# power_ver3.net
KiCad netlist of a schematic drawn in EAGLE
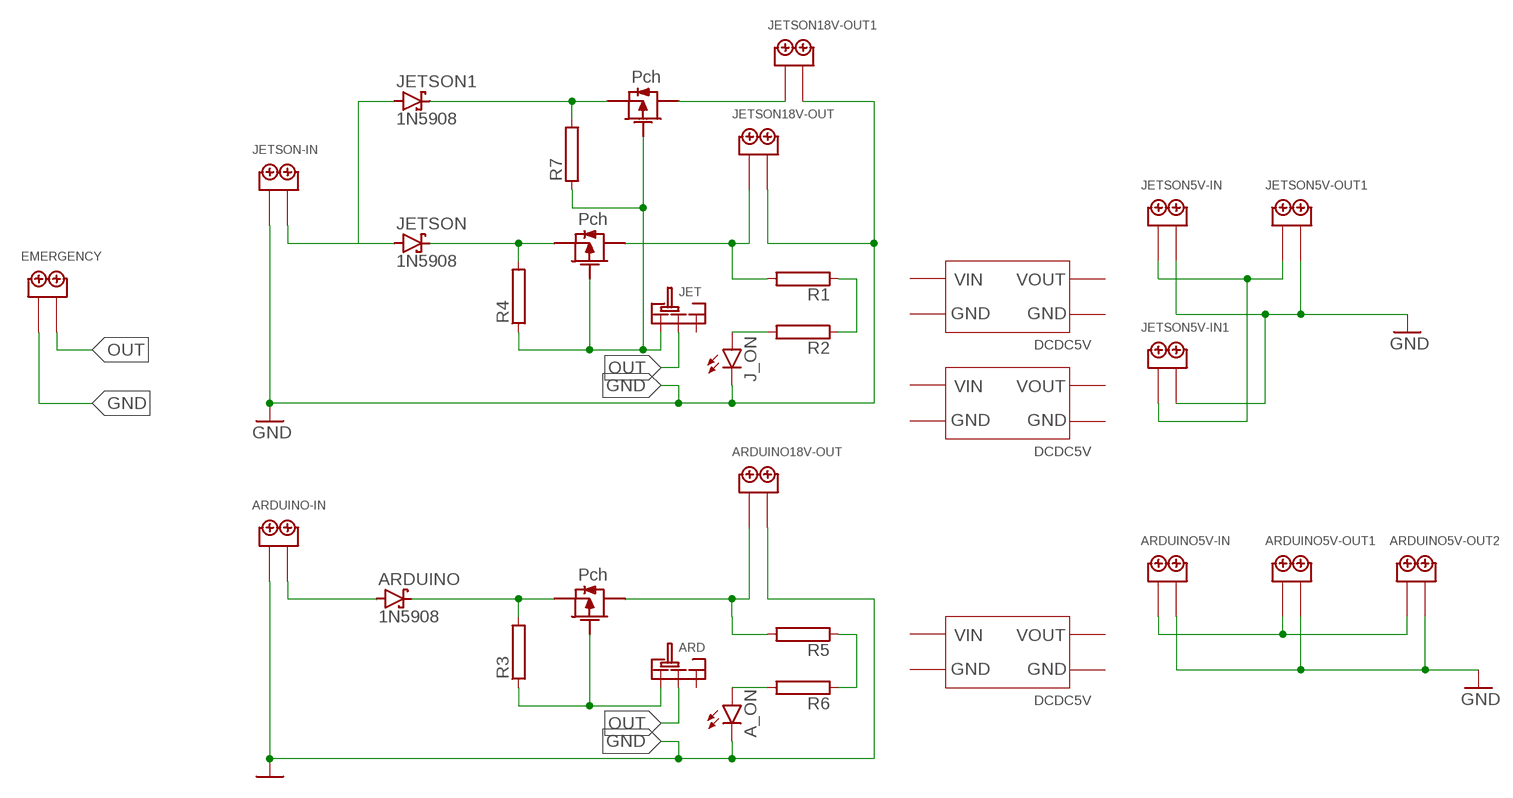
[diagram p0: schematic, sheet 1]

(export (version "E")
  (design (tool "Eeschema 10.0.6"))
  (components
    (comp (ref "ARD")
      (value "SRIDE_SWITCH")
      (footprint "eagle-import:SRIDE_SWITCH")
      (libsource (lib "eagle-import") (part "SRIDE_SWITCH"))
    )
    (comp (ref "ARDUINO")
      (value "1N5908")
      (footprint "eagle-import:C4111-15")
      (libsource (lib "eagle-import") (part "1N5908"))
    )
    (comp (ref "ARDUINO-IN")
      (value "2PIN")
      (footprint "eagle-import:2PIN")
      (libsource (lib "eagle-import") (part "2PIN"))
    )
    (comp (ref "ARDUINO5V-IN")
      (value "2PIN")
      (footprint "eagle-import:2PIN")
      (libsource (lib "eagle-import") (part "2PIN"))
    )
    (comp (ref "ARDUINO5V-OUT1")
      (value "2PIN")
      (footprint "eagle-import:2PIN")
      (libsource (lib "eagle-import") (part "2PIN"))
    )
    (comp (ref "ARDUINO5V-OUT2")
      (value "2PIN")
      (footprint "eagle-import:2PIN")
      (libsource (lib "eagle-import") (part "2PIN"))
    )
    (comp (ref "ARDUINO18V-OUT")
      (value "2PIN")
      (footprint "eagle-import:2PIN")
      (libsource (lib "eagle-import") (part "2PIN"))
    )
    (comp (ref "A_ON")
      (value "LED5MM")
      (footprint "eagle-import:LED5MM")
      (libsource (lib "eagle-import") (part "LED5MM"))
    )
    (comp (ref "EMERGENCY")
      (value "2PIN")
      (footprint "eagle-import:2PIN")
      (libsource (lib "eagle-import") (part "2PIN"))
    )
    (comp (ref "JET")
      (value "SRIDE_SWITCH")
      (footprint "eagle-import:SRIDE_SWITCH")
      (libsource (lib "eagle-import") (part "SRIDE_SWITCH"))
    )
    (comp (ref "JETSON")
      (value "1N5908")
      (footprint "eagle-import:C4111-15")
      (libsource (lib "eagle-import") (part "1N5908"))
    )
    (comp (ref "JETSON-IN")
      (value "2PIN")
      (footprint "eagle-import:2PIN")
      (libsource (lib "eagle-import") (part "2PIN"))
    )
    (comp (ref "JETSON1")
      (value "1N5908")
      (footprint "eagle-import:C4111-15")
      (libsource (lib "eagle-import") (part "1N5908"))
    )
    (comp (ref "JETSON5V-IN")
      (value "2PIN")
      (footprint "eagle-import:2PIN")
      (libsource (lib "eagle-import") (part "2PIN"))
    )
    (comp (ref "JETSON5V-IN1")
      (value "2PIN")
      (footprint "eagle-import:2PIN")
      (libsource (lib "eagle-import") (part "2PIN"))
    )
    (comp (ref "JETSON5V-OUT1")
      (value "2PIN")
      (footprint "eagle-import:2PIN")
      (libsource (lib "eagle-import") (part "2PIN"))
    )
    (comp (ref "JETSON18V-OUT")
      (value "2PIN")
      (footprint "eagle-import:2PIN")
      (libsource (lib "eagle-import") (part "2PIN"))
    )
    (comp (ref "JETSON18V-OUT1")
      (value "2PIN")
      (footprint "eagle-import:2PIN")
      (libsource (lib "eagle-import") (part "2PIN"))
    )
    (comp (ref "J_ON")
      (value "LED5MM")
      (footprint "eagle-import:LED5MM")
      (libsource (lib "eagle-import") (part "LED5MM"))
    )
    (comp (ref "R1")
      (value "RAC01")
      (footprint "eagle-import:AC01")
      (libsource (lib "eagle-import") (part "RAC01"))
    )
    (comp (ref "R2")
      (value "RAC01")
      (footprint "eagle-import:AC01")
      (libsource (lib "eagle-import") (part "RAC01"))
    )
    (comp (ref "R3")
      (value "RAC01")
      (footprint "eagle-import:AC01")
      (libsource (lib "eagle-import") (part "RAC01"))
    )
    (comp (ref "R4")
      (value "RAC01")
      (footprint "eagle-import:AC01")
      (libsource (lib "eagle-import") (part "RAC01"))
    )
    (comp (ref "R5")
      (value "RAC01")
      (footprint "eagle-import:AC01")
      (libsource (lib "eagle-import") (part "RAC01"))
    )
    (comp (ref "R6")
      (value "RAC01")
      (footprint "eagle-import:AC01")
      (libsource (lib "eagle-import") (part "RAC01"))
    )
    (comp (ref "R7")
      (value "RAC01")
      (footprint "eagle-import:AC01")
      (libsource (lib "eagle-import") (part "RAC01"))
    )
    (comp (ref "U$1")
      (value "2SJ334")
      (footprint "eagle-import:2SJ334")
      (libsource (lib "eagle-import") (part "2SJ334"))
    )
    (comp (ref "U$2")
      (value "DCDCDEV")
      (footprint "eagle-import:DCDCDEV")
      (libsource (lib "eagle-import") (part "DCDCDEV"))
    )
    (comp (ref "U$4")
      (value "2SJ334")
      (footprint "eagle-import:2SJ334")
      (libsource (lib "eagle-import") (part "2SJ334"))
    )
    (comp (ref "U$5")
      (value "2SJ334")
      (footprint "eagle-import:2SJ334")
      (libsource (lib "eagle-import") (part "2SJ334"))
    )
    (comp (ref "U$6")
      (value "DCDCDEV")
      (footprint "eagle-import:DCDCDEV")
      (libsource (lib "eagle-import") (part "DCDCDEV"))
    )
    (comp (ref "U$23")
      (value "DCDCDEV")
      (footprint "eagle-import:DCDCDEV")
      (libsource (lib "eagle-import") (part "DCDCDEV"))
    )
  )
  (nets
    (net (code "1") (name "GND") (class "Default")
      (node (ref "ARDUINO-IN") (pin "P$1") (pinfunction "P$1_P$1") (pintype "bidirectional"))
      (node (ref "ARDUINO18V-OUT") (pin "P$2") (pinfunction "P$2_P$2") (pintype "bidirectional"))
      (node (ref "ARDUINO5V-IN") (pin "P$2") (pinfunction "P$2_P$2") (pintype "bidirectional"))
      (node (ref "ARDUINO5V-OUT1") (pin "P$2") (pinfunction "P$2_P$2") (pintype "bidirectional"))
      (node (ref "ARDUINO5V-OUT2") (pin "P$2") (pinfunction "P$2_P$2") (pintype "bidirectional"))
      (node (ref "A_ON") (pin "K") (pinfunction "C_K") (pintype "passive"))
      (node (ref "EMERGENCY") (pin "P$1") (pinfunction "P$1_P$1") (pintype "bidirectional"))
      (node (ref "JETSON-IN") (pin "P$1") (pinfunction "P$1_P$1") (pintype "bidirectional"))
      (node (ref "JETSON18V-OUT") (pin "P$2") (pinfunction "P$2_P$2") (pintype "bidirectional"))
      (node (ref "JETSON18V-OUT1") (pin "P$2") (pinfunction "P$2_P$2") (pintype "bidirectional"))
      (node (ref "JETSON5V-IN") (pin "P$2") (pinfunction "P$2_P$2") (pintype "bidirectional"))
      (node (ref "JETSON5V-IN1") (pin "P$2") (pinfunction "P$2_P$2") (pintype "bidirectional"))
      (node (ref "JETSON5V-OUT1") (pin "P$2") (pinfunction "P$2_P$2") (pintype "bidirectional"))
      (node (ref "J_ON") (pin "K") (pinfunction "C_K") (pintype "passive"))
    )
    (net (code "2") (name "Net-(ARD-PadL)") (class "Default")
      (node (ref "ARD") (pin "L") (pinfunction "L_L") (pintype "bidirectional"))
      (node (ref "R3") (pin "1") (pinfunction "1_1") (pintype "passive"))
      (node (ref "U$5") (pin "GATE") (pinfunction "GATE_GATE") (pintype "bidirectional"))
    )
    (net (code "3") (name "Net-(ARDUINO-IN-PadP$2)") (class "Default")
      (node (ref "ARDUINO") (pin "A") (pinfunction "A_A") (pintype "passive"))
      (node (ref "ARDUINO-IN") (pin "P$2") (pinfunction "P$2_P$2") (pintype "bidirectional"))
    )
    (net (code "4") (name "Net-(ARDUINO-PadC)") (class "Default")
      (node (ref "ARDUINO") (pin "C") (pinfunction "C_C") (pintype "passive"))
      (node (ref "R3") (pin "2") (pinfunction "2_2") (pintype "passive"))
      (node (ref "U$5") (pin "SOURCE") (pinfunction "SOURCE_SOURCE") (pintype "bidirectional"))
    )
    (net (code "5") (name "Net-(ARDUINO5V-IN-PadP$1)") (class "Default")
      (node (ref "ARDUINO5V-IN") (pin "P$1") (pinfunction "P$1_P$1") (pintype "bidirectional"))
      (node (ref "ARDUINO5V-OUT1") (pin "P$1") (pinfunction "P$1_P$1") (pintype "bidirectional"))
      (node (ref "ARDUINO5V-OUT2") (pin "P$1") (pinfunction "P$1_P$1") (pintype "bidirectional"))
    )
    (net (code "6") (name "Net-(ARDUINO18V-OUT-PadP$1)") (class "Default")
      (node (ref "ARDUINO18V-OUT") (pin "P$1") (pinfunction "P$1_P$1") (pintype "bidirectional"))
      (node (ref "R5") (pin "2") (pinfunction "2_2") (pintype "passive"))
      (node (ref "U$5") (pin "DRAIN") (pinfunction "DRAIN_DRAIN") (pintype "bidirectional"))
    )
    (net (code "7") (name "Net-(A_ON-PadA)") (class "Default")
      (node (ref "A_ON") (pin "A") (pinfunction "A_A") (pintype "passive"))
      (node (ref "R6") (pin "2") (pinfunction "2_2") (pintype "passive"))
    )
    (net (code "8") (name "Net-(JET-PadL)") (class "Default")
      (node (ref "JET") (pin "L") (pinfunction "L_L") (pintype "bidirectional"))
      (node (ref "R4") (pin "1") (pinfunction "1_1") (pintype "passive"))
      (node (ref "R7") (pin "1") (pinfunction "1_1") (pintype "passive"))
      (node (ref "U$1") (pin "GATE") (pinfunction "GATE_GATE") (pintype "bidirectional"))
      (node (ref "U$4") (pin "GATE") (pinfunction "GATE_GATE") (pintype "bidirectional"))
    )
    (net (code "9") (name "Net-(JETSON-IN-PadP$2)") (class "Default")
      (node (ref "JETSON") (pin "A") (pinfunction "A_A") (pintype "passive"))
      (node (ref "JETSON-IN") (pin "P$2") (pinfunction "P$2_P$2") (pintype "bidirectional"))
      (node (ref "JETSON1") (pin "A") (pinfunction "A_A") (pintype "passive"))
    )
    (net (code "10") (name "Net-(JETSON-PadC)") (class "Default")
      (node (ref "JETSON") (pin "C") (pinfunction "C_C") (pintype "passive"))
      (node (ref "R4") (pin "2") (pinfunction "2_2") (pintype "passive"))
      (node (ref "U$4") (pin "SOURCE") (pinfunction "SOURCE_SOURCE") (pintype "bidirectional"))
    )
    (net (code "11") (name "Net-(JETSON1-PadC)") (class "Default")
      (node (ref "JETSON1") (pin "C") (pinfunction "C_C") (pintype "passive"))
      (node (ref "R7") (pin "2") (pinfunction "2_2") (pintype "passive"))
      (node (ref "U$1") (pin "SOURCE") (pinfunction "SOURCE_SOURCE") (pintype "bidirectional"))
    )
    (net (code "12") (name "Net-(JETSON5V-IN-PadP$1)") (class "Default")
      (node (ref "JETSON5V-IN") (pin "P$1") (pinfunction "P$1_P$1") (pintype "bidirectional"))
      (node (ref "JETSON5V-IN1") (pin "P$1") (pinfunction "P$1_P$1") (pintype "bidirectional"))
      (node (ref "JETSON5V-OUT1") (pin "P$1") (pinfunction "P$1_P$1") (pintype "bidirectional"))
    )
    (net (code "13") (name "Net-(JETSON18V-OUT-PadP$1)") (class "Default")
      (node (ref "JETSON18V-OUT") (pin "P$1") (pinfunction "P$1_P$1") (pintype "bidirectional"))
      (node (ref "R1") (pin "2") (pinfunction "2_2") (pintype "passive"))
      (node (ref "U$4") (pin "DRAIN") (pinfunction "DRAIN_DRAIN") (pintype "bidirectional"))
    )
    (net (code "14") (name "Net-(JETSON18V-OUT1-PadP$1)") (class "Default")
      (node (ref "JETSON18V-OUT1") (pin "P$1") (pinfunction "P$1_P$1") (pintype "bidirectional"))
      (node (ref "U$1") (pin "DRAIN") (pinfunction "DRAIN_DRAIN") (pintype "bidirectional"))
    )
    (net (code "15") (name "Net-(J_ON-PadA)") (class "Default")
      (node (ref "J_ON") (pin "A") (pinfunction "A_A") (pintype "passive"))
      (node (ref "R2") (pin "2") (pinfunction "2_2") (pintype "passive"))
    )
    (net (code "16") (name "Net-(R1-Pad1)") (class "Default")
      (node (ref "R1") (pin "1") (pinfunction "1_1") (pintype "passive"))
      (node (ref "R2") (pin "1") (pinfunction "1_1") (pintype "passive"))
    )
    (net (code "17") (name "Net-(R5-Pad1)") (class "Default")
      (node (ref "R5") (pin "1") (pinfunction "1_1") (pintype "passive"))
      (node (ref "R6") (pin "1") (pinfunction "1_1") (pintype "passive"))
    )
    (net (code "18") (name "OUT") (class "Default")
      (node (ref "ARD") (pin "LR") (pinfunction "LR_LR") (pintype "bidirectional"))
      (node (ref "EMERGENCY") (pin "P$2") (pinfunction "P$2_P$2") (pintype "bidirectional"))
      (node (ref "JET") (pin "LR") (pinfunction "LR_LR") (pintype "bidirectional"))
    )
    (net (code "19") (name "unconnected-(ARD-PadR)") (class "Default")
      (node (ref "ARD") (pin "R") (pinfunction "R_R") (pintype "bidirectional"))
    )
    (net (code "20") (name "unconnected-(JET-PadR)") (class "Default")
      (node (ref "JET") (pin "R") (pinfunction "R_R") (pintype "bidirectional"))
    )
  )
)
